# Motor.net
KiCad netlist of a schematic drawn in Altium Designer
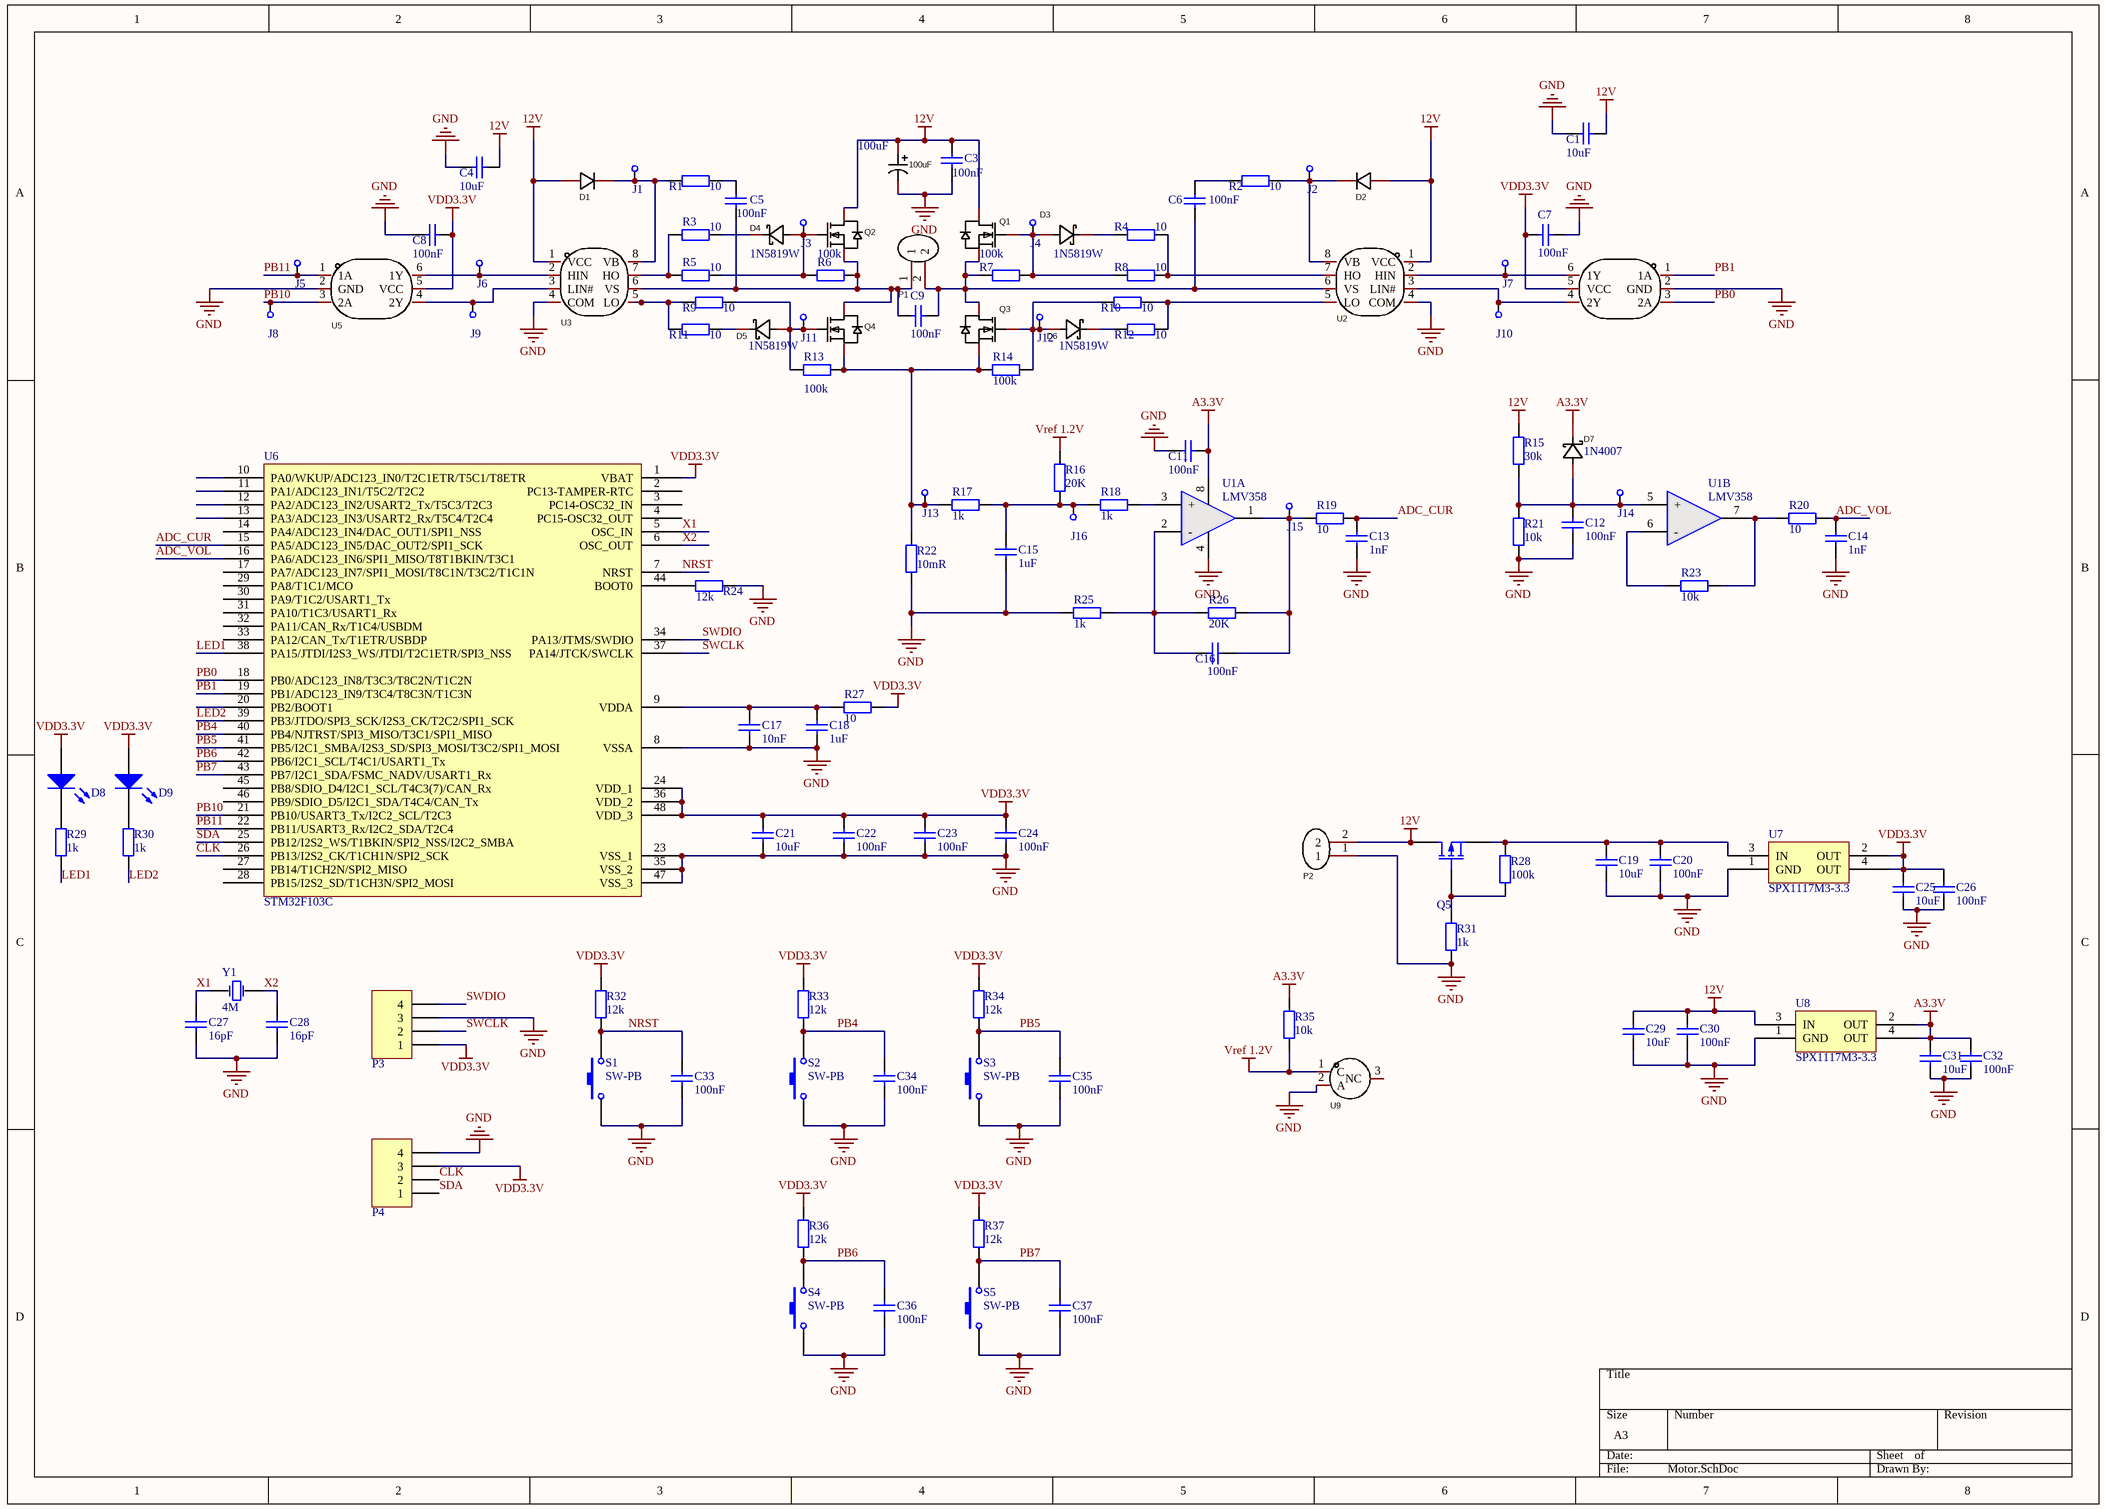
[diagram p0: Motor.SchDoc]

(export (version "E")
  (design (tool "Eeschema 10.0.6"))
  (components
    (comp (ref "C1")
      (value "10uF")
      (footprint "C-RAD-0603")
      (description "无极性电容")
      (fields (field (name "PUBLISHER") "Altium Limited"))
      (libsource (lib "fszhang") (part "Cap"))
    )
    (comp (ref "C2")
      (value "100uF")
      (footprint "CAP-TH_BD5.0-P2.00-D0.5-FD-A")
      (description "贴片和直插电解电容")
      (fields
        (field (name "MANUFACTURER") "KNSCHA(科尼盛)")
        (field (name "MANUFACTURER PART") "RVT47UF50V67RV0029")
        (field (name "ALTIUM_VALUE") "100uF")
      )
      (libsource (lib "fszhang") (part "Cap_1"))
    )
    (comp (ref "C3")
      (value "100nF")
      (footprint "C-RAD-0603")
      (description "无极性电容")
      (fields (field (name "PUBLISHER") "Altium Limited"))
      (libsource (lib "fszhang") (part "Cap"))
    )
    (comp (ref "C4")
      (value "10uF")
      (footprint "C-RAD-0603")
      (description "无极性电容")
      (fields (field (name "PUBLISHER") "Altium Limited"))
      (libsource (lib "fszhang") (part "Cap"))
    )
    (comp (ref "C5")
      (value "100nF")
      (footprint "C-RAD-0603")
      (description "无极性电容")
      (fields (field (name "PUBLISHER") "Altium Limited"))
      (libsource (lib "fszhang") (part "Cap"))
    )
    (comp (ref "C6")
      (value "100nF")
      (footprint "C-RAD-0603")
      (description "无极性电容")
      (fields (field (name "PUBLISHER") "Altium Limited"))
      (libsource (lib "fszhang") (part "Cap"))
    )
    (comp (ref "C7")
      (value "100nF")
      (footprint "C-RAD-0603")
      (description "无极性电容")
      (fields (field (name "PUBLISHER") "Altium Limited"))
      (libsource (lib "fszhang") (part "Cap"))
    )
    (comp (ref "C8")
      (value "100nF")
      (footprint "C-RAD-0603")
      (description "无极性电容")
      (fields (field (name "PUBLISHER") "Altium Limited"))
      (libsource (lib "fszhang") (part "Cap"))
    )
    (comp (ref "C9")
      (value "100nF")
      (footprint "C-RAD-0603")
      (description "无极性电容")
      (fields (field (name "PUBLISHER") "Altium Limited"))
      (libsource (lib "fszhang") (part "Cap"))
    )
    (comp (ref "C11")
      (value "100nF")
      (footprint "C-RAD-0603")
      (description "无极性电容")
      (fields (field (name "PUBLISHER") "Altium Limited"))
      (libsource (lib "fszhang") (part "Cap"))
    )
    (comp (ref "C12")
      (value "100nF")
      (footprint "C-RAD-0603")
      (description "无极性电容")
      (fields (field (name "PUBLISHER") "Altium Limited"))
      (libsource (lib "fszhang") (part "Cap"))
    )
    (comp (ref "C13")
      (value "1nF")
      (footprint "C-RAD-0603")
      (description "无极性电容")
      (fields (field (name "PUBLISHER") "Altium Limited"))
      (libsource (lib "fszhang") (part "Cap"))
    )
    (comp (ref "C14")
      (value "1nF")
      (footprint "C-RAD-0603")
      (description "无极性电容")
      (fields (field (name "PUBLISHER") "Altium Limited"))
      (libsource (lib "fszhang") (part "Cap"))
    )
    (comp (ref "C15")
      (value "1uF")
      (footprint "C-RAD-0603")
      (description "无极性电容")
      (fields (field (name "PUBLISHER") "Altium Limited"))
      (libsource (lib "fszhang") (part "Cap"))
    )
    (comp (ref "C16")
      (value "100nF")
      (footprint "C-RAD-0603")
      (description "无极性电容")
      (fields (field (name "PUBLISHER") "Altium Limited"))
      (libsource (lib "fszhang") (part "Cap"))
    )
    (comp (ref "C17")
      (value "10nF")
      (footprint "C-RAD-0603")
      (description "无极性电容")
      (fields (field (name "PUBLISHER") "Altium Limited"))
      (libsource (lib "fszhang") (part "Cap"))
    )
    (comp (ref "C18")
      (value "1uF")
      (footprint "C-RAD-0603")
      (description "无极性电容")
      (fields (field (name "PUBLISHER") "Altium Limited"))
      (libsource (lib "fszhang") (part "Cap"))
    )
    (comp (ref "C19")
      (value "10uF")
      (footprint "C-RAD-0603")
      (description "无极性电容")
      (fields (field (name "PUBLISHER") "Altium Limited"))
      (libsource (lib "fszhang") (part "Cap"))
    )
    (comp (ref "C20")
      (value "100nF")
      (footprint "C-RAD-0603")
      (description "无极性电容")
      (fields (field (name "PUBLISHER") "Altium Limited"))
      (libsource (lib "fszhang") (part "Cap"))
    )
    (comp (ref "C21")
      (value "10uF")
      (footprint "C-RAD-0603")
      (description "无极性电容")
      (fields (field (name "PUBLISHER") "Altium Limited"))
      (libsource (lib "fszhang") (part "Cap"))
    )
    (comp (ref "C22")
      (value "100nF")
      (footprint "C-RAD-0603")
      (description "无极性电容")
      (fields (field (name "PUBLISHER") "Altium Limited"))
      (libsource (lib "fszhang") (part "Cap"))
    )
    (comp (ref "C23")
      (value "100nF")
      (footprint "C-RAD-0603")
      (description "无极性电容")
      (fields (field (name "PUBLISHER") "Altium Limited"))
      (libsource (lib "fszhang") (part "Cap"))
    )
    (comp (ref "C24")
      (value "100nF")
      (footprint "C-RAD-0603")
      (description "无极性电容")
      (fields (field (name "PUBLISHER") "Altium Limited"))
      (libsource (lib "fszhang") (part "Cap"))
    )
    (comp (ref "C25")
      (value "10uF")
      (footprint "C-RAD-0603")
      (description "无极性电容")
      (fields (field (name "PUBLISHER") "Altium Limited"))
      (libsource (lib "fszhang") (part "Cap"))
    )
    (comp (ref "C26")
      (value "100nF")
      (footprint "C-RAD-0603")
      (description "无极性电容")
      (fields (field (name "PUBLISHER") "Altium Limited"))
      (libsource (lib "fszhang") (part "Cap"))
    )
    (comp (ref "C27")
      (value "16pF")
      (footprint "C-RAD-0603")
      (description "无极性电容")
      (fields (field (name "PUBLISHER") "Altium Limited"))
      (libsource (lib "fszhang") (part "Cap"))
    )
    (comp (ref "C28")
      (value "16pF")
      (footprint "C-RAD-0603")
      (description "无极性电容")
      (fields (field (name "PUBLISHER") "Altium Limited"))
      (libsource (lib "fszhang") (part "Cap"))
    )
    (comp (ref "C29")
      (value "10uF")
      (footprint "C-RAD-0603")
      (description "无极性电容")
      (fields (field (name "PUBLISHER") "Altium Limited"))
      (libsource (lib "fszhang") (part "Cap"))
    )
    (comp (ref "C30")
      (value "100nF")
      (footprint "C-RAD-0603")
      (description "无极性电容")
      (fields (field (name "PUBLISHER") "Altium Limited"))
      (libsource (lib "fszhang") (part "Cap"))
    )
    (comp (ref "C31")
      (value "10uF")
      (footprint "C-RAD-0603")
      (description "无极性电容")
      (fields (field (name "PUBLISHER") "Altium Limited"))
      (libsource (lib "fszhang") (part "Cap"))
    )
    (comp (ref "C32")
      (value "100nF")
      (footprint "C-RAD-0603")
      (description "无极性电容")
      (fields (field (name "PUBLISHER") "Altium Limited"))
      (libsource (lib "fszhang") (part "Cap"))
    )
    (comp (ref "C33")
      (value "100nF")
      (footprint "C-RAD-0603")
      (description "无极性电容")
      (fields (field (name "PUBLISHER") "Altium Limited"))
      (libsource (lib "fszhang") (part "Cap"))
    )
    (comp (ref "C34")
      (value "100nF")
      (footprint "C-RAD-0603")
      (description "无极性电容")
      (fields (field (name "PUBLISHER") "Altium Limited"))
      (libsource (lib "fszhang") (part "Cap"))
    )
    (comp (ref "C35")
      (value "100nF")
      (footprint "C-RAD-0603")
      (description "无极性电容")
      (fields (field (name "PUBLISHER") "Altium Limited"))
      (libsource (lib "fszhang") (part "Cap"))
    )
    (comp (ref "C36")
      (value "100nF")
      (footprint "C-RAD-0603")
      (description "无极性电容")
      (fields (field (name "PUBLISHER") "Altium Limited"))
      (libsource (lib "fszhang") (part "Cap"))
    )
    (comp (ref "C37")
      (value "100nF")
      (footprint "C-RAD-0603")
      (description "无极性电容")
      (fields (field (name "PUBLISHER") "Altium Limited"))
      (libsource (lib "fszhang") (part "Cap"))
    )
    (comp (ref "D1")
      (value "1N4007WS")
      (footprint "SOD-323_L1.8-W1.3-LS2.5-RD")
      (description "二极管")
      (fields (field (name "MANUFACTURER") "MDD"))
      (libsource (lib "fszhang") (part "1N4007WS"))
    )
    (comp (ref "D2")
      (value "1N4007WS")
      (footprint "SOD-323_L1.8-W1.3-LS2.5-RD")
      (description "二极管")
      (fields (field (name "MANUFACTURER") "MDD"))
      (libsource (lib "fszhang") (part "1N4007WS"))
    )
    (comp (ref "D3")
      (value "1N5819W")
      (footprint "SOD-123_L2.7-W1.6-LS3.7-R-RD")
      (description "二极管")
      (fields (field (name "MANUFACTURER") "JSMSEMI(杰盛微)"))
      (libsource (lib "fszhang") (part "1N5819W"))
    )
    (comp (ref "D4")
      (value "1N5819W")
      (footprint "SOD-123_L2.7-W1.6-LS3.7-R-RD")
      (description "二极管")
      (fields (field (name "MANUFACTURER") "JSMSEMI(杰盛微)"))
      (libsource (lib "fszhang") (part "1N5819W"))
    )
    (comp (ref "D5")
      (value "1N5819W")
      (footprint "SOD-123_L2.7-W1.6-LS3.7-R-RD")
      (description "二极管")
      (fields (field (name "MANUFACTURER") "JSMSEMI(杰盛微)"))
      (libsource (lib "fszhang") (part "1N5819W"))
    )
    (comp (ref "D6")
      (value "1N5819W")
      (footprint "SOD-123_L2.7-W1.6-LS3.7-R-RD")
      (description "二极管")
      (fields (field (name "MANUFACTURER") "JSMSEMI(杰盛微)"))
      (libsource (lib "fszhang") (part "1N5819W"))
    )
    (comp (ref "D7")
      (value "1N4007")
      (footprint "SOD-123_L2.7-W1.6-LS3.7-R-RD")
      (description "二极管")
      (fields (field (name "MANUFACTURER") "JSMSEMI(杰盛微)") (field (name "MANUFACTURER PART") "1N5819W"))
      (libsource (lib "fszhang") (part "1N5819W"))
    )
    (comp (ref "D8")
      (value "LED0")
      (footprint "LED_0805")
      (description "发光二极管")
      (fields (field (name "PUBLISHER") "Altium Limited"))
      (libsource (lib "fszhang") (part "LED0"))
    )
    (comp (ref "D9")
      (value "LED0")
      (footprint "LED_0805")
      (description "发光二极管")
      (fields (field (name "PUBLISHER") "Altium Limited"))
      (libsource (lib "fszhang") (part "LED0"))
    )
    (comp (ref "J1")
      (value "CHECK")
      (footprint "CHECK-A")
      (description "测试点")
      (libsource (lib "fszhang") (part "CHECK"))
    )
    (comp (ref "J2")
      (value "CHECK")
      (footprint "CHECK-A")
      (description "测试点")
      (libsource (lib "fszhang") (part "CHECK"))
    )
    (comp (ref "J3")
      (value "CHECK")
      (footprint "CHECK-A")
      (description "测试点")
      (libsource (lib "fszhang") (part "CHECK"))
    )
    (comp (ref "J4")
      (value "CHECK")
      (footprint "CHECK-A")
      (description "测试点")
      (libsource (lib "fszhang") (part "CHECK"))
    )
    (comp (ref "J5")
      (value "CHECK")
      (footprint "CHECK-A")
      (description "测试点")
      (libsource (lib "fszhang") (part "CHECK"))
    )
    (comp (ref "J6")
      (value "CHECK")
      (footprint "CHECK-A")
      (description "测试点")
      (libsource (lib "fszhang") (part "CHECK"))
    )
    (comp (ref "J7")
      (value "CHECK")
      (footprint "CHECK-A")
      (description "测试点")
      (libsource (lib "fszhang") (part "CHECK"))
    )
    (comp (ref "J8")
      (value "CHECK")
      (footprint "CHECK-A")
      (description "测试点")
      (libsource (lib "fszhang") (part "CHECK"))
    )
    (comp (ref "J9")
      (value "CHECK")
      (footprint "CHECK-A")
      (description "测试点")
      (libsource (lib "fszhang") (part "CHECK"))
    )
    (comp (ref "J10")
      (value "CHECK")
      (footprint "CHECK-A")
      (description "测试点")
      (libsource (lib "fszhang") (part "CHECK"))
    )
    (comp (ref "J11")
      (value "CHECK")
      (footprint "CHECK-A")
      (description "测试点")
      (libsource (lib "fszhang") (part "CHECK"))
    )
    (comp (ref "J12")
      (value "CHECK")
      (footprint "CHECK-A")
      (description "测试点")
      (libsource (lib "fszhang") (part "CHECK"))
    )
    (comp (ref "J13")
      (value "CHECK")
      (footprint "CHECK-A")
      (description "测试点")
      (libsource (lib "fszhang") (part "CHECK"))
    )
    (comp (ref "J14")
      (value "CHECK")
      (footprint "CHECK-A")
      (description "测试点")
      (libsource (lib "fszhang") (part "CHECK"))
    )
    (comp (ref "J15")
      (value "CHECK")
      (footprint "CHECK-A")
      (description "测试点")
      (libsource (lib "fszhang") (part "CHECK"))
    )
    (comp (ref "J16")
      (value "CHECK")
      (footprint "CHECK-A")
      (description "测试点")
      (libsource (lib "fszhang") (part "CHECK"))
    )
    (comp (ref "P1")
      (value "WJ500V-5.08-2P")
      (footprint "CONN-TH_2P-P5.00_WJ500V-5.08-2P")
      (description "接线端子")
      (fields (field (name "MANUFACTURER") "KANGNEX(康奈克斯电气)"))
      (libsource (lib "fszhang") (part "WJ500V-5.08-2P"))
    )
    (comp (ref "P2")
      (value "WJ500V-5.08-2P")
      (footprint "CONN-TH_2P-P5.00_WJ500V-5.08-2P")
      (description "接线端子")
      (fields (field (name "MANUFACTURER") "KANGNEX(康奈克斯电气)"))
      (libsource (lib "") (part "WJ500V-5.08-2P_1"))
    )
    (comp (ref "P3")
      (value "Header 4")
      (footprint "HDR4X1_A")
      (description "接插件")
      (fields (field (name "PUBLISHER") "Altium Limited"))
      (libsource (lib "fszhang") (part "Header 4"))
    )
    (comp (ref "P4")
      (value "Header 4")
      (footprint "HDR4X1_A")
      (description "接插件")
      (fields (field (name "PUBLISHER") "Altium Limited"))
      (libsource (lib "fszhang") (part "Header 4"))
    )
    (comp (ref "Q1")
      (value "NCE6020AK")
      (footprint "TO-252-2_L6.6-W6.1-P4.57-LS10.1-TL-CW")
      (description "NMOS")
      (fields (field (name "MANUFACTURER") "NCE(无锡新洁能)"))
      (libsource (lib "fszhang") (part "NCE6020AK"))
    )
    (comp (ref "Q2")
      (value "NCE6020AK")
      (footprint "TO-252-2_L6.6-W6.1-P4.57-LS10.1-TL-CW")
      (description "NMOS")
      (fields (field (name "MANUFACTURER") "NCE(无锡新洁能)"))
      (libsource (lib "fszhang") (part "NCE6020AK"))
    )
    (comp (ref "Q3")
      (value "NCE6020AK")
      (footprint "TO-252-2_L6.6-W6.1-P4.57-LS10.1-TL-CW")
      (description "NMOS")
      (fields (field (name "MANUFACTURER") "NCE(无锡新洁能)"))
      (libsource (lib "fszhang") (part "NCE6020AK"))
    )
    (comp (ref "Q4")
      (value "NCE6020AK")
      (footprint "TO-252-2_L6.6-W6.1-P4.57-LS10.1-TL-CW")
      (description "NMOS")
      (fields (field (name "MANUFACTURER") "NCE(无锡新洁能)"))
      (libsource (lib "fszhang") (part "NCE6020AK"))
    )
    (comp (ref "Q5")
      (value "MOSFET-P")
      (footprint "TO-220AB")
      (description "P-Channel MOSFET")
      (fields (field (name "PUBLISHER") "Altium Limited"))
      (libsource (lib "fszhang") (part "MOSFET-P"))
    )
    (comp (ref "R1")
      (value "10")
      (footprint "0603-1")
      (description "贴片电阻")
      (fields (field (name "PUBLISHER") "Altium Limited"))
      (libsource (lib "") (part "Res1_2"))
    )
    (comp (ref "R2")
      (value "10")
      (footprint "0603-1")
      (description "贴片电阻")
      (fields (field (name "PUBLISHER") "Altium Limited"))
      (libsource (lib "") (part "Res1_2"))
    )
    (comp (ref "R3")
      (value "10")
      (footprint "0603-1")
      (description "贴片电阻")
      (fields (field (name "PUBLISHER") "Altium Limited"))
      (libsource (lib "") (part "Res1_1"))
    )
    (comp (ref "R4")
      (value "10")
      (footprint "0603-1")
      (description "贴片电阻")
      (fields (field (name "PUBLISHER") "Altium Limited"))
      (libsource (lib "") (part "Res1_2"))
    )
    (comp (ref "R5")
      (value "10")
      (footprint "0603-1")
      (description "贴片电阻")
      (fields (field (name "PUBLISHER") "Altium Limited"))
      (libsource (lib "") (part "Res1_1"))
    )
    (comp (ref "R6")
      (value "100k")
      (footprint "0603-1")
      (description "贴片电阻")
      (fields (field (name "PUBLISHER") "Altium Limited"))
      (libsource (lib "") (part "Res1_1"))
    )
    (comp (ref "R7")
      (value "100k")
      (footprint "0603-1")
      (description "贴片电阻")
      (fields (field (name "PUBLISHER") "Altium Limited"))
      (libsource (lib "") (part "Res1_2"))
    )
    (comp (ref "R8")
      (value "10")
      (footprint "0603-1")
      (description "贴片电阻")
      (fields (field (name "PUBLISHER") "Altium Limited"))
      (libsource (lib "") (part "Res1_2"))
    )
    (comp (ref "R9")
      (value "10")
      (footprint "0603-1")
      (description "贴片电阻")
      (fields (field (name "PUBLISHER") "Altium Limited"))
      (libsource (lib "") (part "Res1_1"))
    )
    (comp (ref "R10")
      (value "10")
      (footprint "0603-1")
      (description "贴片电阻")
      (fields (field (name "PUBLISHER") "Altium Limited"))
      (libsource (lib "") (part "Res1_2"))
    )
    (comp (ref "R11")
      (value "10")
      (footprint "0603-1")
      (description "贴片电阻")
      (fields (field (name "PUBLISHER") "Altium Limited"))
      (libsource (lib "") (part "Res1_1"))
    )
    (comp (ref "R12")
      (value "10")
      (footprint "0603-1")
      (description "贴片电阻")
      (fields (field (name "PUBLISHER") "Altium Limited"))
      (libsource (lib "") (part "Res1_2"))
    )
    (comp (ref "R13")
      (value "100k")
      (footprint "0603-1")
      (description "贴片电阻")
      (fields (field (name "PUBLISHER") "Altium Limited"))
      (libsource (lib "") (part "Res1_1"))
    )
    (comp (ref "R14")
      (value "100k")
      (footprint "0603-1")
      (description "贴片电阻")
      (fields (field (name "PUBLISHER") "Altium Limited"))
      (libsource (lib "") (part "Res1_2"))
    )
    (comp (ref "R15")
      (value "30k")
      (footprint "0603-1")
      (description "贴片电阻")
      (fields (field (name "PUBLISHER") "Altium Limited"))
      (libsource (lib "") (part "Res1_3"))
    )
    (comp (ref "R16")
      (value "20K")
      (footprint "0603-1")
      (description "贴片电阻")
      (fields (field (name "PUBLISHER") "Altium Limited"))
      (libsource (lib "") (part "Res1_3"))
    )
    (comp (ref "R17")
      (value "1k")
      (footprint "0603-1")
      (description "贴片电阻")
      (fields (field (name "PUBLISHER") "Altium Limited"))
      (libsource (lib "") (part "Res1_2"))
    )
    (comp (ref "R18")
      (value "1k")
      (footprint "0603-1")
      (description "贴片电阻")
      (fields (field (name "PUBLISHER") "Altium Limited"))
      (libsource (lib "") (part "Res1_2"))
    )
    (comp (ref "R19")
      (value "10")
      (footprint "0603-1")
      (description "贴片电阻")
      (fields (field (name "PUBLISHER") "Altium Limited"))
      (libsource (lib "") (part "Res1_2"))
    )
    (comp (ref "R20")
      (value "10")
      (footprint "0603-1")
      (description "贴片电阻")
      (fields (field (name "PUBLISHER") "Altium Limited"))
      (libsource (lib "") (part "Res1_2"))
    )
    (comp (ref "R21")
      (value "10k")
      (footprint "0603-1")
      (description "贴片电阻")
      (fields (field (name "PUBLISHER") "Altium Limited"))
      (libsource (lib "") (part "Res1_3"))
    )
    (comp (ref "R22")
      (value "10mR")
      (footprint "2512")
      (description "贴片电阻")
      (fields (field (name "PUBLISHER") "Altium Limited"))
      (libsource (lib "fszhang") (part "Res1"))
    )
    (comp (ref "R23")
      (value "10k")
      (footprint "0603-1")
      (description "贴片电阻")
      (fields (field (name "PUBLISHER") "Altium Limited"))
      (libsource (lib "fszhang") (part "Res1"))
    )
    (comp (ref "R24")
      (value "12k")
      (footprint "0603-1")
      (description "贴片电阻")
      (fields (field (name "PUBLISHER") "Altium Limited"))
      (libsource (lib "") (part "Res1_1"))
    )
    (comp (ref "R25")
      (value "1k")
      (footprint "0603-1")
      (description "贴片电阻")
      (fields (field (name "PUBLISHER") "Altium Limited"))
      (libsource (lib "") (part "Res1_2"))
    )
    (comp (ref "R26")
      (value "20K")
      (footprint "0603-1")
      (description "贴片电阻")
      (fields (field (name "PUBLISHER") "Altium Limited"))
      (libsource (lib "") (part "Res1_2"))
    )
    (comp (ref "R27")
      (value "10")
      (footprint "0603-1")
      (description "贴片电阻")
      (fields (field (name "PUBLISHER") "Altium Limited"))
      (libsource (lib "") (part "Res1_1"))
    )
    (comp (ref "R28")
      (value "100k")
      (footprint "0603-1")
      (description "贴片电阻")
      (fields (field (name "Comment") "1k") (field (name "PUBLISHER") "Altium Limited"))
      (libsource (lib "fszhang") (part "Res1"))
    )
    (comp (ref "R29")
      (value "1k")
      (footprint "0603-1")
      (description "贴片电阻")
      (fields (field (name "PUBLISHER") "Altium Limited"))
      (libsource (lib "fszhang") (part "Res1"))
    )
    (comp (ref "R30")
      (value "1k")
      (footprint "0603-1")
      (description "贴片电阻")
      (fields (field (name "PUBLISHER") "Altium Limited"))
      (libsource (lib "fszhang") (part "Res1"))
    )
    (comp (ref "R31")
      (value "1k")
      (footprint "0603-1")
      (description "贴片电阻")
      (fields (field (name "PUBLISHER") "Altium Limited"))
      (libsource (lib "fszhang") (part "Res1"))
    )
    (comp (ref "R32")
      (value "12k")
      (footprint "0603-1")
      (description "贴片电阻")
      (fields (field (name "PUBLISHER") "Altium Limited"))
      (libsource (lib "fszhang") (part "Res1"))
    )
    (comp (ref "R33")
      (value "12k")
      (footprint "0603-1")
      (description "贴片电阻")
      (fields (field (name "PUBLISHER") "Altium Limited"))
      (libsource (lib "fszhang") (part "Res1"))
    )
    (comp (ref "R34")
      (value "12k")
      (footprint "0603-1")
      (description "贴片电阻")
      (fields (field (name "PUBLISHER") "Altium Limited"))
      (libsource (lib "fszhang") (part "Res1"))
    )
    (comp (ref "R35")
      (value "10k")
      (footprint "0603-1")
      (description "贴片电阻")
      (fields (field (name "PUBLISHER") "Altium Limited"))
      (libsource (lib "fszhang") (part "Res1"))
    )
    (comp (ref "R36")
      (value "12k")
      (footprint "0603-1")
      (description "贴片电阻")
      (fields (field (name "PUBLISHER") "Altium Limited"))
      (libsource (lib "fszhang") (part "Res1"))
    )
    (comp (ref "R37")
      (value "12k")
      (footprint "0603-1")
      (description "贴片电阻")
      (fields (field (name "PUBLISHER") "Altium Limited"))
      (libsource (lib "fszhang") (part "Res1"))
    )
    (comp (ref "S1")
      (value "SW-PB")
      (footprint "SW_PB2_A1")
      (description "微动开关")
      (fields (field (name "PUBLISHER") "Altium Limited"))
      (libsource (lib "fszhang") (part "SW-PB"))
    )
    (comp (ref "S2")
      (value "SW-PB")
      (footprint "SW_PB2_A1")
      (description "微动开关")
      (fields (field (name "PUBLISHER") "Altium Limited"))
      (libsource (lib "fszhang") (part "SW-PB"))
    )
    (comp (ref "S3")
      (value "SW-PB")
      (footprint "SW_PB2_A1")
      (description "微动开关")
      (fields (field (name "PUBLISHER") "Altium Limited"))
      (libsource (lib "fszhang") (part "SW-PB"))
    )
    (comp (ref "S4")
      (value "SW-PB")
      (footprint "SW_PB2_A1")
      (description "微动开关")
      (fields (field (name "PUBLISHER") "Altium Limited"))
      (libsource (lib "fszhang") (part "SW-PB"))
    )
    (comp (ref "S5")
      (value "SW-PB")
      (footprint "SW_PB2_A1")
      (description "微动开关")
      (fields (field (name "PUBLISHER") "Altium Limited"))
      (libsource (lib "fszhang") (part "SW-PB"))
    )
    (comp (ref "U1")
      (value "LMV358")
      (footprint "NSO8_N")
      (description "双运放")
      (libsource (lib "fszhang") (part "LM358"))
    )
    (comp (ref "U2")
      (value "XJNG2103")
      (footprint "SOIC-8_L4.9-W3.9-P1.27-LS6.0-BL")
      (description "MOS驱动")
      (fields (field (name "MANUFACTURER") "NCE(无锡新洁能)"))
      (libsource (lib "fszhang") (part "XJNG2103"))
    )
    (comp (ref "U3")
      (value "XJNG2103")
      (footprint "SOIC-8_L4.9-W3.9-P1.27-LS6.0-BL")
      (description "MOS驱动")
      (fields (field (name "MANUFACTURER") "NCE(无锡新洁能)"))
      (libsource (lib "fszhang") (part "XJNG2103"))
    )
    (comp (ref "U4")
      (value "SN74LVC2G17DBVR")
      (footprint "SOT-23-6_L2.9-W1.6-P0.95-LS2.8-BL")
      (description "缓冲器")
      (fields (field (name "MANUFACTURER") "TI(德州仪器)"))
      (libsource (lib "fszhang") (part "SN74LVC2G17DBVR"))
    )
    (comp (ref "U5")
      (value "SN74LVC2G17DBVR")
      (footprint "SOT-23-6_L2.9-W1.6-P0.95-LS2.8-BL")
      (description "缓冲器")
      (fields (field (name "MANUFACTURER") "TI(德州仪器)"))
      (libsource (lib "fszhang") (part "SN74LVC2G17DBVR"))
    )
    (comp (ref "U6")
      (value "STM32F103C")
      (footprint "LQFP-48_M")
      (description "STM32单片机48引脚")
      (libsource (lib "fszhang") (part "STM32F103C"))
    )
    (comp (ref "U7")
      (value "SPX1117M3-3.3")
      (footprint "SOT-223")
      (description "3.3V稳压芯片")
      (libsource (lib "fszhang") (part "SPX1117M3-3.3"))
    )
    (comp (ref "U8")
      (value "SPX1117M3-3.3")
      (footprint "SOT-223")
      (description "3.3V稳压芯片")
      (libsource (lib "fszhang") (part "SPX1117M3-3.3"))
    )
    (comp (ref "U9")
      (value "LM385M3-1.2/TR")
      (footprint "SOT-23-3_L2.9-W1.3-P1.90-LS2.4-BR")
      (fields (field (name "MANUFACTURER") "HGSEMI(华冠)"))
      (libsource (lib "fszhang") (part "LM385M3-1.2/TR"))
    )
    (comp (ref "Y1")
      (value "4M")
      (footprint "HC-49UX-TH_L11.4-W4.7-P4.88")
      (description "晶振")
      (fields (field (name "Comment") "XTAL") (field (name "PUBLISHER") "Altium Limited"))
      (libsource (lib "fszhang") (part "XTAL"))
    )
  )
  (nets
    (net (code "1") (name "/ADC_CUR") (class "Default")
      (node (ref "C13") (pin "1") (pinfunction "1_1") (pintype "passive"))
      (node (ref "R19") (pin "1") (pinfunction "1_1") (pintype "passive"))
      (node (ref "U6") (pin "15") (pinfunction "PA5/ADC123_IN5/DAC_OUT2/SPI1_SCK_15") (pintype "passive"))
    )
    (net (code "2") (name "/ADC_VOL") (class "Default")
      (node (ref "C14") (pin "1") (pinfunction "1_1") (pintype "passive"))
      (node (ref "R20") (pin "1") (pinfunction "1_1") (pintype "passive"))
      (node (ref "U6") (pin "16") (pinfunction "PA6/ADC123_IN6/SPI1_MISO/T8T1BKIN/T3C1_16") (pintype "passive"))
    )
    (net (code "3") (name "/CLK") (class "Default")
      (node (ref "P4") (pin "2") (pinfunction "2_2") (pintype "passive"))
      (node (ref "U6") (pin "26") (pinfunction "PB13/I2S2_CK/T1CH1N/SPI2_SCK_26") (pintype "passive"))
    )
    (net (code "4") (name "/LED1") (class "Default")
      (node (ref "R29") (pin "1") (pinfunction "1_1") (pintype "passive"))
      (node (ref "U6") (pin "38") (pinfunction "PA15/JTDI/I2S3_WS/JTDI/T2C1ETR/SPI3_NSS_38") (pintype "passive"))
    )
    (net (code "5") (name "/LED2") (class "Default")
      (node (ref "R30") (pin "1") (pinfunction "1_1") (pintype "passive"))
      (node (ref "U6") (pin "39") (pinfunction "PB3/JTDO/SPI3_SCK/I2S3_CK/T2C2/SPI1_SCK_39") (pintype "passive"))
    )
    (net (code "6") (name "/NRST") (class "Default")
      (node (ref "C33") (pin "2") (pinfunction "2_2") (pintype "passive"))
      (node (ref "R32") (pin "1") (pinfunction "1_1") (pintype "passive"))
      (node (ref "S1") (pin "2") (pinfunction "2_2") (pintype "passive"))
      (node (ref "U6") (pin "7") (pinfunction "NRST_7") (pintype "passive"))
    )
    (net (code "7") (name "/PB0") (class "Default")
      (node (ref "U4") (pin "3") (pinfunction "2A_3") (pintype "passive"))
      (node (ref "U6") (pin "18") (pinfunction "PB0/ADC123_IN8/T3C3/T8C2N/T1C2N_18") (pintype "passive"))
    )
    (net (code "8") (name "/PB1") (class "Default")
      (node (ref "U4") (pin "1") (pinfunction "1A_1") (pintype "passive"))
      (node (ref "U6") (pin "19") (pinfunction "PB1/ADC123_IN9/T3C4/T8C3N/T1C3N_19") (pintype "passive"))
    )
    (net (code "9") (name "/PB4") (class "Default")
      (node (ref "C34") (pin "2") (pinfunction "2_2") (pintype "passive"))
      (node (ref "R33") (pin "1") (pinfunction "1_1") (pintype "passive"))
      (node (ref "S2") (pin "2") (pinfunction "2_2") (pintype "passive"))
      (node (ref "U6") (pin "40") (pinfunction "PB4/NJTRST/SPI3_MISO/T3C1/SPI1_MISO_40") (pintype "passive"))
    )
    (net (code "10") (name "/PB5") (class "Default")
      (node (ref "C35") (pin "2") (pinfunction "2_2") (pintype "passive"))
      (node (ref "R34") (pin "1") (pinfunction "1_1") (pintype "passive"))
      (node (ref "S3") (pin "2") (pinfunction "2_2") (pintype "passive"))
      (node (ref "U6") (pin "41") (pinfunction "PB5/I2C1_SMBA/I2S3_SD/SPI3_MOSI/T3C2/SPI1_MOSI_41") (pintype "passive"))
    )
    (net (code "11") (name "/PB6") (class "Default")
      (node (ref "C36") (pin "2") (pinfunction "2_2") (pintype "passive"))
      (node (ref "R36") (pin "1") (pinfunction "1_1") (pintype "passive"))
      (node (ref "S4") (pin "2") (pinfunction "2_2") (pintype "passive"))
      (node (ref "U6") (pin "42") (pinfunction "PB6/I2C1_SCL/T4C1/USART1_Tx_42") (pintype "passive"))
    )
    (net (code "12") (name "/PB7") (class "Default")
      (node (ref "C37") (pin "2") (pinfunction "2_2") (pintype "passive"))
      (node (ref "R37") (pin "1") (pinfunction "1_1") (pintype "passive"))
      (node (ref "S5") (pin "2") (pinfunction "2_2") (pintype "passive"))
      (node (ref "U6") (pin "43") (pinfunction "PB7/I2C1_SDA/FSMC_NADV/USART1_Rx_43") (pintype "passive"))
    )
    (net (code "13") (name "/PB10") (class "Default")
      (node (ref "J8") (pin "1") (pinfunction "1_1") (pintype "passive"))
      (node (ref "U5") (pin "3") (pinfunction "2A_3") (pintype "passive"))
      (node (ref "U6") (pin "21") (pinfunction "PB10/USART3_Tx/I2C2_SCL/T2C3_21") (pintype "passive"))
    )
    (net (code "14") (name "/PB11") (class "Default")
      (node (ref "J5") (pin "1") (pinfunction "1_1") (pintype "passive"))
      (node (ref "U5") (pin "1") (pinfunction "1A_1") (pintype "passive"))
      (node (ref "U6") (pin "22") (pinfunction "PB11/USART3_Rx/I2C2_SDA/T2C4_22") (pintype "passive"))
    )
    (net (code "15") (name "/SDA") (class "Default")
      (node (ref "P4") (pin "1") (pinfunction "1_1") (pintype "passive"))
      (node (ref "U6") (pin "25") (pinfunction "PB12/I2S2_WS/T1BKIN/SPI2_NSS/I2C2_SMBA_25") (pintype "passive"))
    )
    (net (code "16") (name "/SWCLK") (class "Default")
      (node (ref "P3") (pin "2") (pinfunction "2_2") (pintype "passive"))
      (node (ref "U6") (pin "37") (pinfunction "PA14/JTCK/SWCLK_37") (pintype "passive"))
    )
    (net (code "17") (name "/SWDIO") (class "Default")
      (node (ref "P3") (pin "4") (pinfunction "4_4") (pintype "passive"))
      (node (ref "U6") (pin "34") (pinfunction "PA13/JTMS/SWDIO_34") (pintype "passive"))
    )
    (net (code "18") (name "/X1") (class "Default")
      (node (ref "C27") (pin "2") (pinfunction "2_2") (pintype "passive"))
      (node (ref "U6") (pin "5") (pinfunction "OSC_IN_5") (pintype "passive"))
      (node (ref "Y1") (pin "2") (pinfunction "OSC2_2") (pintype "passive"))
    )
    (net (code "19") (name "/X2") (class "Default")
      (node (ref "C28") (pin "2") (pinfunction "2_2") (pintype "passive"))
      (node (ref "U6") (pin "6") (pinfunction "OSC_OUT_6") (pintype "passive"))
      (node (ref "Y1") (pin "1") (pinfunction "OSC1_1") (pintype "passive"))
    )
    (net (code "20") (name "12V") (class "Default")
      (node (ref "C1") (pin "1") (pinfunction "1_1") (pintype "passive"))
      (node (ref "C2") (pin "1") (pinfunction "1_1") (pintype "passive"))
      (node (ref "C29") (pin "2") (pinfunction "2_2") (pintype "passive"))
      (node (ref "C3") (pin "2") (pinfunction "2_2") (pintype "passive"))
      (node (ref "C30") (pin "2") (pinfunction "2_2") (pintype "passive"))
      (node (ref "C4") (pin "1") (pinfunction "1_1") (pintype "passive"))
      (node (ref "D1") (pin "2") (pinfunction "A_2") (pintype "passive"))
      (node (ref "D2") (pin "2") (pinfunction "A_2") (pintype "passive"))
      (node (ref "P2") (pin "2") (pinfunction "2_2") (pintype "passive"))
      (node (ref "Q1") (pin "2") (pinfunction "D_2") (pintype "passive"))
      (node (ref "Q2") (pin "2") (pinfunction "D_2") (pintype "passive"))
      (node (ref "Q5") (pin "D") (pinfunction "D_D") (pintype "passive"))
      (node (ref "R15") (pin "1") (pinfunction "1_1") (pintype "passive"))
      (node (ref "U2") (pin "1") (pinfunction "VCC_1") (pintype "passive"))
      (node (ref "U3") (pin "1") (pinfunction "VCC_1") (pintype "passive"))
      (node (ref "U8") (pin "3") (pinfunction "IN_3") (pintype "passive"))
    )
    (net (code "21") (name "A3.3V") (class "Default")
      (node (ref "C11") (pin "1") (pinfunction "1_1") (pintype "passive"))
      (node (ref "C31") (pin "2") (pinfunction "2_2") (pintype "passive"))
      (node (ref "C32") (pin "2") (pinfunction "2_2") (pintype "passive"))
      (node (ref "D7") (pin "2") (pinfunction "C_2") (pintype "passive"))
      (node (ref "R35") (pin "2") (pinfunction "2_2") (pintype "passive"))
      (node (ref "U1") (pin "8") (pinfunction "V+_8") (pintype "power_in"))
      (node (ref "U8") (pin "2") (pinfunction "OUT_2") (pintype "passive"))
      (node (ref "U8") (pin "4") (pinfunction "OUT_4") (pintype "passive"))
    )
    (net (code "22") (name "GND") (class "Default")
      (node (ref "C1") (pin "2") (pinfunction "2_2") (pintype "passive"))
      (node (ref "C11") (pin "2") (pinfunction "2_2") (pintype "passive"))
      (node (ref "C12") (pin "2") (pinfunction "2_2") (pintype "passive"))
      (node (ref "C13") (pin "2") (pinfunction "2_2") (pintype "passive"))
      (node (ref "C14") (pin "2") (pinfunction "2_2") (pintype "passive"))
      (node (ref "C15") (pin "1") (pinfunction "1_1") (pintype "passive"))
      (node (ref "C17") (pin "1") (pinfunction "1_1") (pintype "passive"))
      (node (ref "C18") (pin "1") (pinfunction "1_1") (pintype "passive"))
      (node (ref "C19") (pin "1") (pinfunction "1_1") (pintype "passive"))
      (node (ref "C2") (pin "2") (pinfunction "2_2") (pintype "passive"))
      (node (ref "C20") (pin "1") (pinfunction "1_1") (pintype "passive"))
      (node (ref "C21") (pin "1") (pinfunction "1_1") (pintype "passive"))
      (node (ref "C22") (pin "1") (pinfunction "1_1") (pintype "passive"))
      (node (ref "C23") (pin "1") (pinfunction "1_1") (pintype "passive"))
      (node (ref "C24") (pin "1") (pinfunction "1_1") (pintype "passive"))
      (node (ref "C25") (pin "1") (pinfunction "1_1") (pintype "passive"))
      (node (ref "C26") (pin "1") (pinfunction "1_1") (pintype "passive"))
      (node (ref "C27") (pin "1") (pinfunction "1_1") (pintype "passive"))
      (node (ref "C28") (pin "1") (pinfunction "1_1") (pintype "passive"))
      (node (ref "C29") (pin "1") (pinfunction "1_1") (pintype "passive"))
      (node (ref "C3") (pin "1") (pinfunction "1_1") (pintype "passive"))
      (node (ref "C30") (pin "1") (pinfunction "1_1") (pintype "passive"))
      (node (ref "C31") (pin "1") (pinfunction "1_1") (pintype "passive"))
      (node (ref "C32") (pin "1") (pinfunction "1_1") (pintype "passive"))
      (node (ref "C33") (pin "1") (pinfunction "1_1") (pintype "passive"))
      (node (ref "C34") (pin "1") (pinfunction "1_1") (pintype "passive"))
      (node (ref "C35") (pin "1") (pinfunction "1_1") (pintype "passive"))
      (node (ref "C36") (pin "1") (pinfunction "1_1") (pintype "passive"))
      (node (ref "C37") (pin "1") (pinfunction "1_1") (pintype "passive"))
      (node (ref "C4") (pin "2") (pinfunction "2_2") (pintype "passive"))
      (node (ref "C7") (pin "2") (pinfunction "2_2") (pintype "passive"))
      (node (ref "C8") (pin "2") (pinfunction "2_2") (pintype "passive"))
      (node (ref "P2") (pin "1") (pinfunction "1_1") (pintype "passive"))
      (node (ref "P3") (pin "3") (pinfunction "3_3") (pintype "passive"))
      (node (ref "P4") (pin "4") (pinfunction "4_4") (pintype "passive"))
      (node (ref "R21") (pin "2") (pinfunction "2_2") (pintype "passive"))
      (node (ref "R22") (pin "1") (pinfunction "1_1") (pintype "passive"))
      (node (ref "R24") (pin "2") (pinfunction "2_2") (pintype "passive"))
      (node (ref "R25") (pin "2") (pinfunction "2_2") (pintype "passive"))
      (node (ref "R31") (pin "1") (pinfunction "1_1") (pintype "passive"))
      (node (ref "S1") (pin "1") (pinfunction "1_1") (pintype "passive"))
      (node (ref "S2") (pin "1") (pinfunction "1_1") (pintype "passive"))
      (node (ref "S3") (pin "1") (pinfunction "1_1") (pintype "passive"))
      (node (ref "S4") (pin "1") (pinfunction "1_1") (pintype "passive"))
      (node (ref "S5") (pin "1") (pinfunction "1_1") (pintype "passive"))
      (node (ref "U1") (pin "4") (pinfunction "V-_4") (pintype "power_in"))
      (node (ref "U2") (pin "4") (pinfunction "COM_4") (pintype "passive"))
      (node (ref "U3") (pin "4") (pinfunction "COM_4") (pintype "passive"))
      (node (ref "U4") (pin "2") (pinfunction "GND_2") (pintype "passive"))
      (node (ref "U5") (pin "2") (pinfunction "GND_2") (pintype "passive"))
      (node (ref "U6") (pin "23") (pinfunction "VSS_1_23") (pintype "passive"))
      (node (ref "U6") (pin "35") (pinfunction "VSS_2_35") (pintype "passive"))
      (node (ref "U6") (pin "47") (pinfunction "VSS_3_47") (pintype "passive"))
      (node (ref "U6") (pin "8") (pinfunction "VSSA_8") (pintype "passive"))
      (node (ref "U7") (pin "1") (pinfunction "GND_1") (pintype "passive"))
      (node (ref "U8") (pin "1") (pinfunction "GND_1") (pintype "passive"))
      (node (ref "U9") (pin "2") (pinfunction "A_2") (pintype "passive"))
    )
    (net (code "23") (name "Net-(C5-Pad2)") (class "Default")
      (node (ref "C5") (pin "2") (pinfunction "2_2") (pintype "passive"))
      (node (ref "R1") (pin "1") (pinfunction "1_1") (pintype "passive"))
    )
    (net (code "24") (name "Net-(C6-Pad2)") (class "Default")
      (node (ref "C6") (pin "2") (pinfunction "2_2") (pintype "passive"))
      (node (ref "R2") (pin "2") (pinfunction "2_2") (pintype "passive"))
    )
    (net (code "25") (name "Net-(C15-Pad2)") (class "Default")
      (node (ref "C15") (pin "2") (pinfunction "2_2") (pintype "passive"))
      (node (ref "J16") (pin "1") (pinfunction "1_1") (pintype "passive"))
      (node (ref "R16") (pin "2") (pinfunction "2_2") (pintype "passive"))
      (node (ref "R17") (pin "1") (pinfunction "1_1") (pintype "passive"))
      (node (ref "R18") (pin "2") (pinfunction "2_2") (pintype "passive"))
    )
    (net (code "26") (name "Net-(D1-K)") (class "Default")
      (node (ref "D1") (pin "1") (pinfunction "K_1") (pintype "passive"))
      (node (ref "J1") (pin "1") (pinfunction "1_1") (pintype "passive"))
      (node (ref "R1") (pin "2") (pinfunction "2_2") (pintype "passive"))
      (node (ref "U3") (pin "8") (pinfunction "VB_8") (pintype "passive"))
    )
    (net (code "27") (name "Net-(D2-K)") (class "Default")
      (node (ref "D2") (pin "1") (pinfunction "K_1") (pintype "passive"))
      (node (ref "J2") (pin "1") (pinfunction "1_1") (pintype "passive"))
      (node (ref "R2") (pin "1") (pinfunction "1_1") (pintype "passive"))
      (node (ref "U2") (pin "8") (pinfunction "VB_8") (pintype "passive"))
    )
    (net (code "28") (name "Net-(D3-A)") (class "Default")
      (node (ref "D3") (pin "1") (pinfunction "A_1") (pintype "passive"))
      (node (ref "J4") (pin "1") (pinfunction "1_1") (pintype "passive"))
      (node (ref "Q1") (pin "1") (pinfunction "G_1") (pintype "passive"))
      (node (ref "R7") (pin "1") (pinfunction "1_1") (pintype "passive"))
      (node (ref "R8") (pin "2") (pinfunction "2_2") (pintype "passive"))
    )
    (net (code "29") (name "Net-(D3-C)") (class "Default")
      (node (ref "D3") (pin "2") (pinfunction "C_2") (pintype "passive"))
      (node (ref "R4") (pin "2") (pinfunction "2_2") (pintype "passive"))
    )
    (net (code "30") (name "Net-(D4-A)") (class "Default")
      (node (ref "D4") (pin "1") (pinfunction "A_1") (pintype "passive"))
      (node (ref "J3") (pin "1") (pinfunction "1_1") (pintype "passive"))
      (node (ref "Q2") (pin "1") (pinfunction "G_1") (pintype "passive"))
      (node (ref "R5") (pin "2") (pinfunction "2_2") (pintype "passive"))
      (node (ref "R6") (pin "1") (pinfunction "1_1") (pintype "passive"))
    )
    (net (code "31") (name "Net-(D4-C)") (class "Default")
      (node (ref "D4") (pin "2") (pinfunction "C_2") (pintype "passive"))
      (node (ref "R3") (pin "2") (pinfunction "2_2") (pintype "passive"))
    )
    (net (code "32") (name "Net-(D5-A)") (class "Default")
      (node (ref "D5") (pin "1") (pinfunction "A_1") (pintype "passive"))
      (node (ref "J11") (pin "1") (pinfunction "1_1") (pintype "passive"))
      (node (ref "Q4") (pin "1") (pinfunction "G_1") (pintype "passive"))
      (node (ref "R13") (pin "1") (pinfunction "1_1") (pintype "passive"))
      (node (ref "R9") (pin "2") (pinfunction "2_2") (pintype "passive"))
    )
    (net (code "33") (name "Net-(D5-C)") (class "Default")
      (node (ref "D5") (pin "2") (pinfunction "C_2") (pintype "passive"))
      (node (ref "R11") (pin "2") (pinfunction "2_2") (pintype "passive"))
    )
    (net (code "34") (name "Net-(D6-A)") (class "Default")
      (node (ref "D6") (pin "1") (pinfunction "A_1") (pintype "passive"))
      (node (ref "J12") (pin "1") (pinfunction "1_1") (pintype "passive"))
      (node (ref "Q3") (pin "1") (pinfunction "G_1") (pintype "passive"))
      (node (ref "R10") (pin "2") (pinfunction "2_2") (pintype "passive"))
      (node (ref "R14") (pin "1") (pinfunction "1_1") (pintype "passive"))
    )
    (net (code "35") (name "Net-(D6-C)") (class "Default")
      (node (ref "D6") (pin "2") (pinfunction "C_2") (pintype "passive"))
      (node (ref "R12") (pin "2") (pinfunction "2_2") (pintype "passive"))
    )
    (net (code "36") (name "Net-(D7-A)") (class "Default")
      (node (ref "C12") (pin "1") (pinfunction "1_1") (pintype "passive"))
      (node (ref "D7") (pin "1") (pinfunction "A_1") (pintype "passive"))
      (node (ref "J14") (pin "1") (pinfunction "1_1") (pintype "passive"))
      (node (ref "R15") (pin "2") (pinfunction "2_2") (pintype "passive"))
      (node (ref "R21") (pin "1") (pinfunction "1_1") (pintype "passive"))
      (node (ref "U1") (pin "5") (pinfunction "+_5") (pintype "passive"))
    )
    (net (code "37") (name "Net-(D8-K)") (class "Default")
      (node (ref "D8") (pin "2") (pinfunction "K_2") (pintype "passive"))
      (node (ref "R29") (pin "2") (pinfunction "2_2") (pintype "passive"))
    )
    (net (code "38") (name "Net-(D9-K)") (class "Default")
      (node (ref "D9") (pin "2") (pinfunction "K_2") (pintype "passive"))
      (node (ref "R30") (pin "2") (pinfunction "2_2") (pintype "passive"))
    )
    (net (code "39") (name "Net-(Q1-S)") (class "Default")
      (node (ref "C6") (pin "1") (pinfunction "1_1") (pintype "passive"))
      (node (ref "C9") (pin "1") (pinfunction "1_1") (pintype "passive"))
      (node (ref "P1") (pin "2") (pinfunction "2_2") (pintype "passive"))
      (node (ref "Q1") (pin "3") (pinfunction "S_3") (pintype "passive"))
      (node (ref "Q3") (pin "2") (pinfunction "D_2") (pintype "passive"))
      (node (ref "R7") (pin "2") (pinfunction "2_2") (pintype "passive"))
      (node (ref "U2") (pin "6") (pinfunction "VS_6") (pintype "passive"))
    )
    (net (code "40") (name "Net-(Q2-S)") (class "Default")
      (node (ref "C5") (pin "1") (pinfunction "1_1") (pintype "passive"))
      (node (ref "C9") (pin "2") (pinfunction "2_2") (pintype "passive"))
      (node (ref "P1") (pin "1") (pinfunction "1_1") (pintype "passive"))
      (node (ref "Q2") (pin "3") (pinfunction "S_3") (pintype "passive"))
      (node (ref "Q4") (pin "2") (pinfunction "D_2") (pintype "passive"))
      (node (ref "R6") (pin "2") (pinfunction "2_2") (pintype "passive"))
      (node (ref "U3") (pin "6") (pinfunction "VS_6") (pintype "passive"))
    )
    (net (code "41") (name "Net-(Q3-S)") (class "Default")
      (node (ref "J13") (pin "1") (pinfunction "1_1") (pintype "passive"))
      (node (ref "Q3") (pin "3") (pinfunction "S_3") (pintype "passive"))
      (node (ref "Q4") (pin "3") (pinfunction "S_3") (pintype "passive"))
      (node (ref "R13") (pin "2") (pinfunction "2_2") (pintype "passive"))
      (node (ref "R14") (pin "2") (pinfunction "2_2") (pintype "passive"))
      (node (ref "R17") (pin "2") (pinfunction "2_2") (pintype "passive"))
      (node (ref "R22") (pin "2") (pinfunction "2_2") (pintype "passive"))
    )
    (net (code "42") (name "Net-(Q5-PadG)") (class "Default")
      (node (ref "Q5") (pin "G") (pinfunction "G_G") (pintype "passive"))
      (node (ref "R28") (pin "1") (pinfunction "1_1") (pintype "passive"))
      (node (ref "R31") (pin "2") (pinfunction "2_2") (pintype "passive"))
    )
    (net (code "43") (name "Net-(U1A-+)") (class "Default")
      (node (ref "R18") (pin "1") (pinfunction "1_1") (pintype "passive"))
      (node (ref "U1") (pin "3") (pinfunction "+_3") (pintype "passive"))
    )
    (net (code "44") (name "Net-(U1A--)") (class "Default")
      (node (ref "C16") (pin "2") (pinfunction "2_2") (pintype "passive"))
      (node (ref "R25") (pin "1") (pinfunction "1_1") (pintype "passive"))
      (node (ref "R26") (pin "2") (pinfunction "2_2") (pintype "passive"))
      (node (ref "U1") (pin "2") (pinfunction "-_2") (pintype "passive"))
    )
    (net (code "45") (name "Net-(U1A-OUT1)") (class "Default")
      (node (ref "C16") (pin "1") (pinfunction "1_1") (pintype "passive"))
      (node (ref "J15") (pin "1") (pinfunction "1_1") (pintype "passive"))
      (node (ref "R19") (pin "2") (pinfunction "2_2") (pintype "passive"))
      (node (ref "R26") (pin "1") (pinfunction "1_1") (pintype "passive"))
      (node (ref "U1") (pin "1") (pinfunction "OUT1_1") (pintype "passive"))
    )
    (net (code "46") (name "Net-(U1B--)") (class "Default")
      (node (ref "R23") (pin "1") (pinfunction "1_1") (pintype "passive"))
      (node (ref "U1") (pin "6") (pinfunction "-_6") (pintype "passive"))
    )
    (net (code "47") (name "Net-(U1B-OUT2)") (class "Default")
      (node (ref "R20") (pin "2") (pinfunction "2_2") (pintype "passive"))
      (node (ref "R23") (pin "2") (pinfunction "2_2") (pintype "passive"))
      (node (ref "U1") (pin "7") (pinfunction "OUT2_7") (pintype "passive"))
    )
    (net (code "48") (name "Net-(U2-HIN)") (class "Default")
      (node (ref "J7") (pin "1") (pinfunction "1_1") (pintype "passive"))
      (node (ref "U2") (pin "2") (pinfunction "HIN_2") (pintype "passive"))
      (node (ref "U4") (pin "6") (pinfunction "1Y_6") (pintype "passive"))
    )
    (net (code "49") (name "Net-(U2-HO)") (class "Default")
      (node (ref "R4") (pin "1") (pinfunction "1_1") (pintype "passive"))
      (node (ref "R8") (pin "1") (pinfunction "1_1") (pintype "passive"))
      (node (ref "U2") (pin "7") (pinfunction "HO_7") (pintype "passive"))
    )
    (net (code "50") (name "Net-(U2-LIN#)") (class "Default")
      (node (ref "J10") (pin "1") (pinfunction "1_1") (pintype "passive"))
      (node (ref "U2") (pin "3") (pinfunction "LIN#_3") (pintype "passive"))
      (node (ref "U4") (pin "4") (pinfunction "2Y_4") (pintype "passive"))
    )
    (net (code "51") (name "Net-(U2-LO)") (class "Default")
      (node (ref "R10") (pin "1") (pinfunction "1_1") (pintype "passive"))
      (node (ref "R12") (pin "1") (pinfunction "1_1") (pintype "passive"))
      (node (ref "U2") (pin "5") (pinfunction "LO_5") (pintype "passive"))
    )
    (net (code "52") (name "Net-(U3-HIN)") (class "Default")
      (node (ref "J6") (pin "1") (pinfunction "1_1") (pintype "passive"))
      (node (ref "U3") (pin "2") (pinfunction "HIN_2") (pintype "passive"))
      (node (ref "U5") (pin "6") (pinfunction "1Y_6") (pintype "passive"))
    )
    (net (code "53") (name "Net-(U3-HO)") (class "Default")
      (node (ref "R3") (pin "1") (pinfunction "1_1") (pintype "passive"))
      (node (ref "R5") (pin "1") (pinfunction "1_1") (pintype "passive"))
      (node (ref "U3") (pin "7") (pinfunction "HO_7") (pintype "passive"))
    )
    (net (code "54") (name "Net-(U3-LIN#)") (class "Default")
      (node (ref "J9") (pin "1") (pinfunction "1_1") (pintype "passive"))
      (node (ref "U3") (pin "3") (pinfunction "LIN#_3") (pintype "passive"))
      (node (ref "U5") (pin "4") (pinfunction "2Y_4") (pintype "passive"))
    )
    (net (code "55") (name "Net-(U3-LO)") (class "Default")
      (node (ref "R11") (pin "1") (pinfunction "1_1") (pintype "passive"))
      (node (ref "R9") (pin "1") (pinfunction "1_1") (pintype "passive"))
      (node (ref "U3") (pin "5") (pinfunction "LO_5") (pintype "passive"))
    )
    (net (code "56") (name "Net-(U6-BOOT0)") (class "Default")
      (node (ref "R24") (pin "1") (pinfunction "1_1") (pintype "passive"))
      (node (ref "U6") (pin "44") (pinfunction "BOOT0_44") (pintype "passive"))
    )
    (net (code "57") (name "Net-(U6-VDDA)") (class "Default")
      (node (ref "C17") (pin "2") (pinfunction "2_2") (pintype "passive"))
      (node (ref "C18") (pin "2") (pinfunction "2_2") (pintype "passive"))
      (node (ref "R27") (pin "1") (pinfunction "1_1") (pintype "passive"))
      (node (ref "U6") (pin "9") (pinfunction "VDDA_9") (pintype "passive"))
    )
    (net (code "58") (name "Net-(U7-IN)") (class "Default")
      (node (ref "C19") (pin "2") (pinfunction "2_2") (pintype "passive"))
      (node (ref "C20") (pin "2") (pinfunction "2_2") (pintype "passive"))
      (node (ref "Q5") (pin "S") (pinfunction "S_S") (pintype "passive"))
      (node (ref "R28") (pin "2") (pinfunction "2_2") (pintype "passive"))
      (node (ref "U7") (pin "3") (pinfunction "IN_3") (pintype "passive"))
    )
    (net (code "59") (name "VDD3.3V") (class "Default")
      (node (ref "C21") (pin "2") (pinfunction "2_2") (pintype "passive"))
      (node (ref "C22") (pin "2") (pinfunction "2_2") (pintype "passive"))
      (node (ref "C23") (pin "2") (pinfunction "2_2") (pintype "passive"))
      (node (ref "C24") (pin "2") (pinfunction "2_2") (pintype "passive"))
      (node (ref "C25") (pin "2") (pinfunction "2_2") (pintype "passive"))
      (node (ref "C26") (pin "2") (pinfunction "2_2") (pintype "passive"))
      (node (ref "C7") (pin "1") (pinfunction "1_1") (pintype "passive"))
      (node (ref "C8") (pin "1") (pinfunction "1_1") (pintype "passive"))
      (node (ref "D8") (pin "1") (pinfunction "A_1") (pintype "passive"))
      (node (ref "D9") (pin "1") (pinfunction "A_1") (pintype "passive"))
      (node (ref "P3") (pin "1") (pinfunction "1_1") (pintype "passive"))
      (node (ref "P4") (pin "3") (pinfunction "3_3") (pintype "passive"))
      (node (ref "R27") (pin "2") (pinfunction "2_2") (pintype "passive"))
      (node (ref "R32") (pin "2") (pinfunction "2_2") (pintype "passive"))
      (node (ref "R33") (pin "2") (pinfunction "2_2") (pintype "passive"))
      (node (ref "R34") (pin "2") (pinfunction "2_2") (pintype "passive"))
      (node (ref "R36") (pin "2") (pinfunction "2_2") (pintype "passive"))
      (node (ref "R37") (pin "2") (pinfunction "2_2") (pintype "passive"))
      (node (ref "U4") (pin "5") (pinfunction "VCC_5") (pintype "passive"))
      (node (ref "U5") (pin "5") (pinfunction "VCC_5") (pintype "passive"))
      (node (ref "U6") (pin "1") (pinfunction "VBAT_1") (pintype "passive"))
      (node (ref "U6") (pin "24") (pinfunction "VDD_1_24") (pintype "passive"))
      (node (ref "U6") (pin "36") (pinfunction "VDD_2_36") (pintype "passive"))
      (node (ref "U6") (pin "48") (pinfunction "VDD_3_48") (pintype "passive"))
      (node (ref "U7") (pin "2") (pinfunction "OUT_2") (pintype "passive"))
      (node (ref "U7") (pin "4") (pinfunction "OUT_4") (pintype "passive"))
    )
    (net (code "60") (name "Vref 1.2V") (class "Default")
      (node (ref "R16") (pin "1") (pinfunction "1_1") (pintype "passive"))
      (node (ref "R35") (pin "1") (pinfunction "1_1") (pintype "passive"))
      (node (ref "U9") (pin "1") (pinfunction "C_1") (pintype "passive"))
    )
    (net (code "61") (name "unconnected-(U6-PA0{slash}WKUP{slash}ADC123_IN0{slash}T2C1ETR{slash}T5C1{slash}T8ETR-Pad10)") (class "Default")
      (node (ref "U6") (pin "10") (pinfunction "PA0/WKUP/ADC123_IN0/T2C1ETR/T5C1/T8ETR_10") (pintype "passive"))
    )
    (net (code "62") (name "unconnected-(U6-PA1{slash}ADC123_IN1{slash}T5C2{slash}T2C2-Pad11)") (class "Default")
      (node (ref "U6") (pin "11") (pinfunction "PA1/ADC123_IN1/T5C2/T2C2_11") (pintype "passive"))
    )
    (net (code "63") (name "unconnected-(U6-PA2{slash}ADC123_IN2{slash}USART2_Tx{slash}T5C3{slash}T2C3-Pad12)") (class "Default")
      (node (ref "U6") (pin "12") (pinfunction "PA2/ADC123_IN2/USART2_Tx/T5C3/T2C3_12") (pintype "passive"))
    )
    (net (code "64") (name "unconnected-(U6-PA3{slash}ADC123_IN3{slash}USART2_Rx{slash}T5C4{slash}T2C4-Pad13)") (class "Default")
      (node (ref "U6") (pin "13") (pinfunction "PA3/ADC123_IN3/USART2_Rx/T5C4/T2C4_13") (pintype "passive"))
    )
    (net (code "65") (name "unconnected-(U6-PA4{slash}ADC123_IN4{slash}DAC_OUT1{slash}SPI1_NSS-Pad14)") (class "Default")
      (node (ref "U6") (pin "14") (pinfunction "PA4/ADC123_IN4/DAC_OUT1/SPI1_NSS_14") (pintype "passive"))
    )
    (net (code "66") (name "unconnected-(U6-PA7{slash}ADC123_IN7{slash}SPI1_MOSI{slash}T8C1N{slash}T3C2{slash}T1C1N-Pad17)") (class "Default")
      (node (ref "U6") (pin "17") (pinfunction "PA7/ADC123_IN7/SPI1_MOSI/T8C1N/T3C2/T1C1N_17") (pintype "passive"))
    )
    (net (code "67") (name "unconnected-(U6-PA8{slash}T1C1{slash}MCO-Pad29)") (class "Default")
      (node (ref "U6") (pin "29") (pinfunction "PA8/T1C1/MCO_29") (pintype "passive"))
    )
    (net (code "68") (name "unconnected-(U6-PA9{slash}T1C2{slash}USART1_Tx-Pad30)") (class "Default")
      (node (ref "U6") (pin "30") (pinfunction "PA9/T1C2/USART1_Tx_30") (pintype "passive"))
    )
    (net (code "69") (name "unconnected-(U6-PA10{slash}T1C3{slash}USART1_Rx-Pad31)") (class "Default")
      (node (ref "U6") (pin "31") (pinfunction "PA10/T1C3/USART1_Rx_31") (pintype "passive"))
    )
    (net (code "70") (name "unconnected-(U6-PA11{slash}CAN_Rx{slash}T1C4{slash}USBDM-Pad32)") (class "Default")
      (node (ref "U6") (pin "32") (pinfunction "PA11/CAN_Rx/T1C4/USBDM_32") (pintype "passive"))
    )
    (net (code "71") (name "unconnected-(U6-PA12{slash}CAN_Tx{slash}T1ETR{slash}USBDP-Pad33)") (class "Default")
      (node (ref "U6") (pin "33") (pinfunction "PA12/CAN_Tx/T1ETR/USBDP_33") (pintype "passive"))
    )
    (net (code "72") (name "unconnected-(U6-PB2{slash}BOOT1-Pad20)") (class "Default")
      (node (ref "U6") (pin "20") (pinfunction "PB2/BOOT1_20") (pintype "passive"))
    )
    (net (code "73") (name "unconnected-(U6-PB8{slash}SDIO_D4{slash}I2C1_SCL{slash}T4C3(7){slash}CAN_Rx-Pad45)") (class "Default")
      (node (ref "U6") (pin "45") (pinfunction "PB8/SDIO_D4/I2C1_SCL/T4C3(7)/CAN_Rx_45") (pintype "passive"))
    )
    (net (code "74") (name "unconnected-(U6-PB9{slash}SDIO_D5{slash}I2C1_SDA{slash}T4C4{slash}CAN_Tx-Pad46)") (class "Default")
      (node (ref "U6") (pin "46") (pinfunction "PB9/SDIO_D5/I2C1_SDA/T4C4/CAN_Tx_46") (pintype "passive"))
    )
    (net (code "75") (name "unconnected-(U6-PB14{slash}T1CH2N{slash}SPI2_MISO-Pad27)") (class "Default")
      (node (ref "U6") (pin "27") (pinfunction "PB14/T1CH2N/SPI2_MISO_27") (pintype "passive"))
    )
    (net (code "76") (name "unconnected-(U6-PB15{slash}I2S2_SD{slash}T1CH3N{slash}SPI2_MOSI-Pad28)") (class "Default")
      (node (ref "U6") (pin "28") (pinfunction "PB15/I2S2_SD/T1CH3N/SPI2_MOSI_28") (pintype "passive"))
    )
    (net (code "77") (name "unconnected-(U6-PC13-TAMPER-RTC-Pad2)") (class "Default")
      (node (ref "U6") (pin "2") (pinfunction "PC13-TAMPER-RTC_2") (pintype "passive"))
    )
    (net (code "78") (name "unconnected-(U6-PC14-OSC32_IN-Pad3)") (class "Default")
      (node (ref "U6") (pin "3") (pinfunction "PC14-OSC32_IN_3") (pintype "passive"))
    )
    (net (code "79") (name "unconnected-(U6-PC15-OSC32_OUT-Pad4)") (class "Default")
      (node (ref "U6") (pin "4") (pinfunction "PC15-OSC32_OUT_4") (pintype "passive"))
    )
    (net (code "80") (name "unconnected-(U9-NC-Pad3)") (class "Default")
      (node (ref "U9") (pin "3") (pinfunction "NC_3") (pintype "passive"))
    )
  )
)
